# schematic.net
KiCad netlist of a schematic drawn in EAGLE
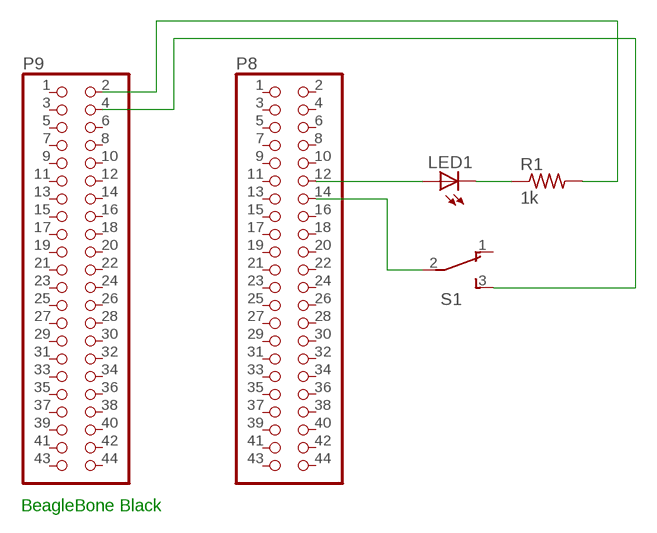
[diagram p0: schematic, sheet 1]

(export (version "E")
  (design (tool "Eeschema 10.0.6"))
  (components
    (comp (ref "LED1")
      (value "LED5MM")
      (footprint "eagle-import:LED5MM")
      (libsource (lib "eagle-import") (part "LED5MM"))
    )
    (comp (ref "P8")
      (value "PINHD-2X22")
      (footprint "eagle-import:2X22")
      (libsource (lib "eagle-import") (part "PINHD-2X22"))
    )
    (comp (ref "P9")
      (value "PINHD-2X22")
      (footprint "eagle-import:2X22")
      (libsource (lib "eagle-import") (part "PINHD-2X22"))
    )
    (comp (ref "R1")
      (value "1k")
      (footprint "eagle-import:0204_7")
      (libsource (lib "eagle-import") (part "R-US_0204/7"))
    )
    (comp (ref "S1")
      (value "TL36PO")
      (footprint "eagle-import:TL3XPO")
      (libsource (lib "eagle-import") (part "TL36PO"))
    )
  )
  (nets
    (net (code "1") (name "Net-(LED1-C)") (class "Default")
      (node (ref "LED1") (pin "K") (pinfunction "C_K") (pintype "passive"))
      (node (ref "R1") (pin "1") (pinfunction "1_1") (pintype "passive"))
    )
    (net (code "2") (name "Net-(LED1-PadA)") (class "Default")
      (node (ref "LED1") (pin "A") (pinfunction "A_A") (pintype "passive"))
      (node (ref "P8") (pin "12") (pinfunction "12_12") (pintype "passive"))
    )
    (net (code "3") (name "Net-(P9-Pad2)") (class "Default")
      (node (ref "P9") (pin "2") (pinfunction "2_2") (pintype "passive"))
      (node (ref "R1") (pin "2") (pinfunction "2_2") (pintype "passive"))
    )
    (net (code "4") (name "Net-(S1-P)") (class "Default")
      (node (ref "P8") (pin "14") (pinfunction "14_14") (pintype "passive"))
      (node (ref "S1") (pin "2") (pinfunction "P_2") (pintype "passive"))
    )
    (net (code "5") (name "Net-(S1-S)") (class "Default")
      (node (ref "P9") (pin "4") (pinfunction "4_4") (pintype "passive"))
      (node (ref "S1") (pin "3") (pinfunction "S_3") (pintype "passive"))
    )
    (net (code "6") (name "unconnected-(P8-Pad1)") (class "Default")
      (node (ref "P8") (pin "1") (pinfunction "1_1") (pintype "passive"))
    )
    (net (code "7") (name "unconnected-(P8-Pad2)") (class "Default")
      (node (ref "P8") (pin "2") (pinfunction "2_2") (pintype "passive"))
    )
    (net (code "8") (name "unconnected-(P8-Pad3)") (class "Default")
      (node (ref "P8") (pin "3") (pinfunction "3_3") (pintype "passive"))
    )
    (net (code "9") (name "unconnected-(P8-Pad4)") (class "Default")
      (node (ref "P8") (pin "4") (pinfunction "4_4") (pintype "passive"))
    )
    (net (code "10") (name "unconnected-(P8-Pad5)") (class "Default")
      (node (ref "P8") (pin "5") (pinfunction "5_5") (pintype "passive"))
    )
    (net (code "11") (name "unconnected-(P8-Pad6)") (class "Default")
      (node (ref "P8") (pin "6") (pinfunction "6_6") (pintype "passive"))
    )
    (net (code "12") (name "unconnected-(P8-Pad7)") (class "Default")
      (node (ref "P8") (pin "7") (pinfunction "7_7") (pintype "passive"))
    )
    (net (code "13") (name "unconnected-(P8-Pad8)") (class "Default")
      (node (ref "P8") (pin "8") (pinfunction "8_8") (pintype "passive"))
    )
    (net (code "14") (name "unconnected-(P8-Pad9)") (class "Default")
      (node (ref "P8") (pin "9") (pinfunction "9_9") (pintype "passive"))
    )
    (net (code "15") (name "unconnected-(P8-Pad10)") (class "Default")
      (node (ref "P8") (pin "10") (pinfunction "10_10") (pintype "passive"))
    )
    (net (code "16") (name "unconnected-(P8-Pad11)") (class "Default")
      (node (ref "P8") (pin "11") (pinfunction "11_11") (pintype "passive"))
    )
    (net (code "17") (name "unconnected-(P8-Pad13)") (class "Default")
      (node (ref "P8") (pin "13") (pinfunction "13_13") (pintype "passive"))
    )
    (net (code "18") (name "unconnected-(P8-Pad15)") (class "Default")
      (node (ref "P8") (pin "15") (pinfunction "15_15") (pintype "passive"))
    )
    (net (code "19") (name "unconnected-(P8-Pad16)") (class "Default")
      (node (ref "P8") (pin "16") (pinfunction "16_16") (pintype "passive"))
    )
    (net (code "20") (name "unconnected-(P8-Pad17)") (class "Default")
      (node (ref "P8") (pin "17") (pinfunction "17_17") (pintype "passive"))
    )
    (net (code "21") (name "unconnected-(P8-Pad18)") (class "Default")
      (node (ref "P8") (pin "18") (pinfunction "18_18") (pintype "passive"))
    )
    (net (code "22") (name "unconnected-(P8-Pad19)") (class "Default")
      (node (ref "P8") (pin "19") (pinfunction "19_19") (pintype "passive"))
    )
    (net (code "23") (name "unconnected-(P8-Pad20)") (class "Default")
      (node (ref "P8") (pin "20") (pinfunction "20_20") (pintype "passive"))
    )
    (net (code "24") (name "unconnected-(P8-Pad21)") (class "Default")
      (node (ref "P8") (pin "21") (pinfunction "21_21") (pintype "passive"))
    )
    (net (code "25") (name "unconnected-(P8-Pad22)") (class "Default")
      (node (ref "P8") (pin "22") (pinfunction "22_22") (pintype "passive"))
    )
    (net (code "26") (name "unconnected-(P8-Pad23)") (class "Default")
      (node (ref "P8") (pin "23") (pinfunction "23_23") (pintype "passive"))
    )
    (net (code "27") (name "unconnected-(P8-Pad24)") (class "Default")
      (node (ref "P8") (pin "24") (pinfunction "24_24") (pintype "passive"))
    )
    (net (code "28") (name "unconnected-(P8-Pad25)") (class "Default")
      (node (ref "P8") (pin "25") (pinfunction "25_25") (pintype "passive"))
    )
    (net (code "29") (name "unconnected-(P8-Pad26)") (class "Default")
      (node (ref "P8") (pin "26") (pinfunction "26_26") (pintype "passive"))
    )
    (net (code "30") (name "unconnected-(P8-Pad27)") (class "Default")
      (node (ref "P8") (pin "27") (pinfunction "27_27") (pintype "passive"))
    )
    (net (code "31") (name "unconnected-(P8-Pad28)") (class "Default")
      (node (ref "P8") (pin "28") (pinfunction "28_28") (pintype "passive"))
    )
    (net (code "32") (name "unconnected-(P8-Pad29)") (class "Default")
      (node (ref "P8") (pin "29") (pinfunction "29_29") (pintype "passive"))
    )
    (net (code "33") (name "unconnected-(P8-Pad30)") (class "Default")
      (node (ref "P8") (pin "30") (pinfunction "30_30") (pintype "passive"))
    )
    (net (code "34") (name "unconnected-(P8-Pad31)") (class "Default")
      (node (ref "P8") (pin "31") (pinfunction "31_31") (pintype "passive"))
    )
    (net (code "35") (name "unconnected-(P8-Pad32)") (class "Default")
      (node (ref "P8") (pin "32") (pinfunction "32_32") (pintype "passive"))
    )
    (net (code "36") (name "unconnected-(P8-Pad33)") (class "Default")
      (node (ref "P8") (pin "33") (pinfunction "33_33") (pintype "passive"))
    )
    (net (code "37") (name "unconnected-(P8-Pad34)") (class "Default")
      (node (ref "P8") (pin "34") (pinfunction "34_34") (pintype "passive"))
    )
    (net (code "38") (name "unconnected-(P8-Pad35)") (class "Default")
      (node (ref "P8") (pin "35") (pinfunction "35_35") (pintype "passive"))
    )
    (net (code "39") (name "unconnected-(P8-Pad36)") (class "Default")
      (node (ref "P8") (pin "36") (pinfunction "36_36") (pintype "passive"))
    )
    (net (code "40") (name "unconnected-(P8-Pad37)") (class "Default")
      (node (ref "P8") (pin "37") (pinfunction "37_37") (pintype "passive"))
    )
    (net (code "41") (name "unconnected-(P8-Pad38)") (class "Default")
      (node (ref "P8") (pin "38") (pinfunction "38_38") (pintype "passive"))
    )
    (net (code "42") (name "unconnected-(P8-Pad39)") (class "Default")
      (node (ref "P8") (pin "39") (pinfunction "39_39") (pintype "passive"))
    )
    (net (code "43") (name "unconnected-(P8-Pad40)") (class "Default")
      (node (ref "P8") (pin "40") (pinfunction "40_40") (pintype "passive"))
    )
    (net (code "44") (name "unconnected-(P8-Pad41)") (class "Default")
      (node (ref "P8") (pin "41") (pinfunction "41_41") (pintype "passive"))
    )
    (net (code "45") (name "unconnected-(P8-Pad42)") (class "Default")
      (node (ref "P8") (pin "42") (pinfunction "42_42") (pintype "passive"))
    )
    (net (code "46") (name "unconnected-(P8-Pad43)") (class "Default")
      (node (ref "P8") (pin "43") (pinfunction "43_43") (pintype "passive"))
    )
    (net (code "47") (name "unconnected-(P8-Pad44)") (class "Default")
      (node (ref "P8") (pin "44") (pinfunction "44_44") (pintype "passive"))
    )
    (net (code "48") (name "unconnected-(P9-Pad1)") (class "Default")
      (node (ref "P9") (pin "1") (pinfunction "1_1") (pintype "passive"))
    )
    (net (code "49") (name "unconnected-(P9-Pad3)") (class "Default")
      (node (ref "P9") (pin "3") (pinfunction "3_3") (pintype "passive"))
    )
    (net (code "50") (name "unconnected-(P9-Pad5)") (class "Default")
      (node (ref "P9") (pin "5") (pinfunction "5_5") (pintype "passive"))
    )
    (net (code "51") (name "unconnected-(P9-Pad6)") (class "Default")
      (node (ref "P9") (pin "6") (pinfunction "6_6") (pintype "passive"))
    )
    (net (code "52") (name "unconnected-(P9-Pad7)") (class "Default")
      (node (ref "P9") (pin "7") (pinfunction "7_7") (pintype "passive"))
    )
    (net (code "53") (name "unconnected-(P9-Pad8)") (class "Default")
      (node (ref "P9") (pin "8") (pinfunction "8_8") (pintype "passive"))
    )
    (net (code "54") (name "unconnected-(P9-Pad9)") (class "Default")
      (node (ref "P9") (pin "9") (pinfunction "9_9") (pintype "passive"))
    )
    (net (code "55") (name "unconnected-(P9-Pad10)") (class "Default")
      (node (ref "P9") (pin "10") (pinfunction "10_10") (pintype "passive"))
    )
    (net (code "56") (name "unconnected-(P9-Pad11)") (class "Default")
      (node (ref "P9") (pin "11") (pinfunction "11_11") (pintype "passive"))
    )
    (net (code "57") (name "unconnected-(P9-Pad12)") (class "Default")
      (node (ref "P9") (pin "12") (pinfunction "12_12") (pintype "passive"))
    )
    (net (code "58") (name "unconnected-(P9-Pad13)") (class "Default")
      (node (ref "P9") (pin "13") (pinfunction "13_13") (pintype "passive"))
    )
    (net (code "59") (name "unconnected-(P9-Pad14)") (class "Default")
      (node (ref "P9") (pin "14") (pinfunction "14_14") (pintype "passive"))
    )
    (net (code "60") (name "unconnected-(P9-Pad15)") (class "Default")
      (node (ref "P9") (pin "15") (pinfunction "15_15") (pintype "passive"))
    )
    (net (code "61") (name "unconnected-(P9-Pad16)") (class "Default")
      (node (ref "P9") (pin "16") (pinfunction "16_16") (pintype "passive"))
    )
    (net (code "62") (name "unconnected-(P9-Pad17)") (class "Default")
      (node (ref "P9") (pin "17") (pinfunction "17_17") (pintype "passive"))
    )
    (net (code "63") (name "unconnected-(P9-Pad18)") (class "Default")
      (node (ref "P9") (pin "18") (pinfunction "18_18") (pintype "passive"))
    )
    (net (code "64") (name "unconnected-(P9-Pad19)") (class "Default")
      (node (ref "P9") (pin "19") (pinfunction "19_19") (pintype "passive"))
    )
    (net (code "65") (name "unconnected-(P9-Pad20)") (class "Default")
      (node (ref "P9") (pin "20") (pinfunction "20_20") (pintype "passive"))
    )
    (net (code "66") (name "unconnected-(P9-Pad21)") (class "Default")
      (node (ref "P9") (pin "21") (pinfunction "21_21") (pintype "passive"))
    )
    (net (code "67") (name "unconnected-(P9-Pad22)") (class "Default")
      (node (ref "P9") (pin "22") (pinfunction "22_22") (pintype "passive"))
    )
    (net (code "68") (name "unconnected-(P9-Pad23)") (class "Default")
      (node (ref "P9") (pin "23") (pinfunction "23_23") (pintype "passive"))
    )
    (net (code "69") (name "unconnected-(P9-Pad24)") (class "Default")
      (node (ref "P9") (pin "24") (pinfunction "24_24") (pintype "passive"))
    )
    (net (code "70") (name "unconnected-(P9-Pad25)") (class "Default")
      (node (ref "P9") (pin "25") (pinfunction "25_25") (pintype "passive"))
    )
    (net (code "71") (name "unconnected-(P9-Pad26)") (class "Default")
      (node (ref "P9") (pin "26") (pinfunction "26_26") (pintype "passive"))
    )
    (net (code "72") (name "unconnected-(P9-Pad27)") (class "Default")
      (node (ref "P9") (pin "27") (pinfunction "27_27") (pintype "passive"))
    )
    (net (code "73") (name "unconnected-(P9-Pad28)") (class "Default")
      (node (ref "P9") (pin "28") (pinfunction "28_28") (pintype "passive"))
    )
    (net (code "74") (name "unconnected-(P9-Pad29)") (class "Default")
      (node (ref "P9") (pin "29") (pinfunction "29_29") (pintype "passive"))
    )
    (net (code "75") (name "unconnected-(P9-Pad30)") (class "Default")
      (node (ref "P9") (pin "30") (pinfunction "30_30") (pintype "passive"))
    )
    (net (code "76") (name "unconnected-(P9-Pad31)") (class "Default")
      (node (ref "P9") (pin "31") (pinfunction "31_31") (pintype "passive"))
    )
    (net (code "77") (name "unconnected-(P9-Pad32)") (class "Default")
      (node (ref "P9") (pin "32") (pinfunction "32_32") (pintype "passive"))
    )
    (net (code "78") (name "unconnected-(P9-Pad33)") (class "Default")
      (node (ref "P9") (pin "33") (pinfunction "33_33") (pintype "passive"))
    )
    (net (code "79") (name "unconnected-(P9-Pad34)") (class "Default")
      (node (ref "P9") (pin "34") (pinfunction "34_34") (pintype "passive"))
    )
    (net (code "80") (name "unconnected-(P9-Pad35)") (class "Default")
      (node (ref "P9") (pin "35") (pinfunction "35_35") (pintype "passive"))
    )
    (net (code "81") (name "unconnected-(P9-Pad36)") (class "Default")
      (node (ref "P9") (pin "36") (pinfunction "36_36") (pintype "passive"))
    )
    (net (code "82") (name "unconnected-(P9-Pad37)") (class "Default")
      (node (ref "P9") (pin "37") (pinfunction "37_37") (pintype "passive"))
    )
    (net (code "83") (name "unconnected-(P9-Pad38)") (class "Default")
      (node (ref "P9") (pin "38") (pinfunction "38_38") (pintype "passive"))
    )
    (net (code "84") (name "unconnected-(P9-Pad39)") (class "Default")
      (node (ref "P9") (pin "39") (pinfunction "39_39") (pintype "passive"))
    )
    (net (code "85") (name "unconnected-(P9-Pad40)") (class "Default")
      (node (ref "P9") (pin "40") (pinfunction "40_40") (pintype "passive"))
    )
    (net (code "86") (name "unconnected-(P9-Pad41)") (class "Default")
      (node (ref "P9") (pin "41") (pinfunction "41_41") (pintype "passive"))
    )
    (net (code "87") (name "unconnected-(P9-Pad42)") (class "Default")
      (node (ref "P9") (pin "42") (pinfunction "42_42") (pintype "passive"))
    )
    (net (code "88") (name "unconnected-(P9-Pad43)") (class "Default")
      (node (ref "P9") (pin "43") (pinfunction "43_43") (pintype "passive"))
    )
    (net (code "89") (name "unconnected-(P9-Pad44)") (class "Default")
      (node (ref "P9") (pin "44") (pinfunction "44_44") (pintype "passive"))
    )
    (net (code "90") (name "unconnected-(S1-O-Pad1)") (class "Default")
      (node (ref "S1") (pin "1") (pinfunction "O_1") (pintype "passive"))
    )
  )
)
